# SensorBoardSchm.net
KiCad netlist of a schematic drawn in Altium Designer
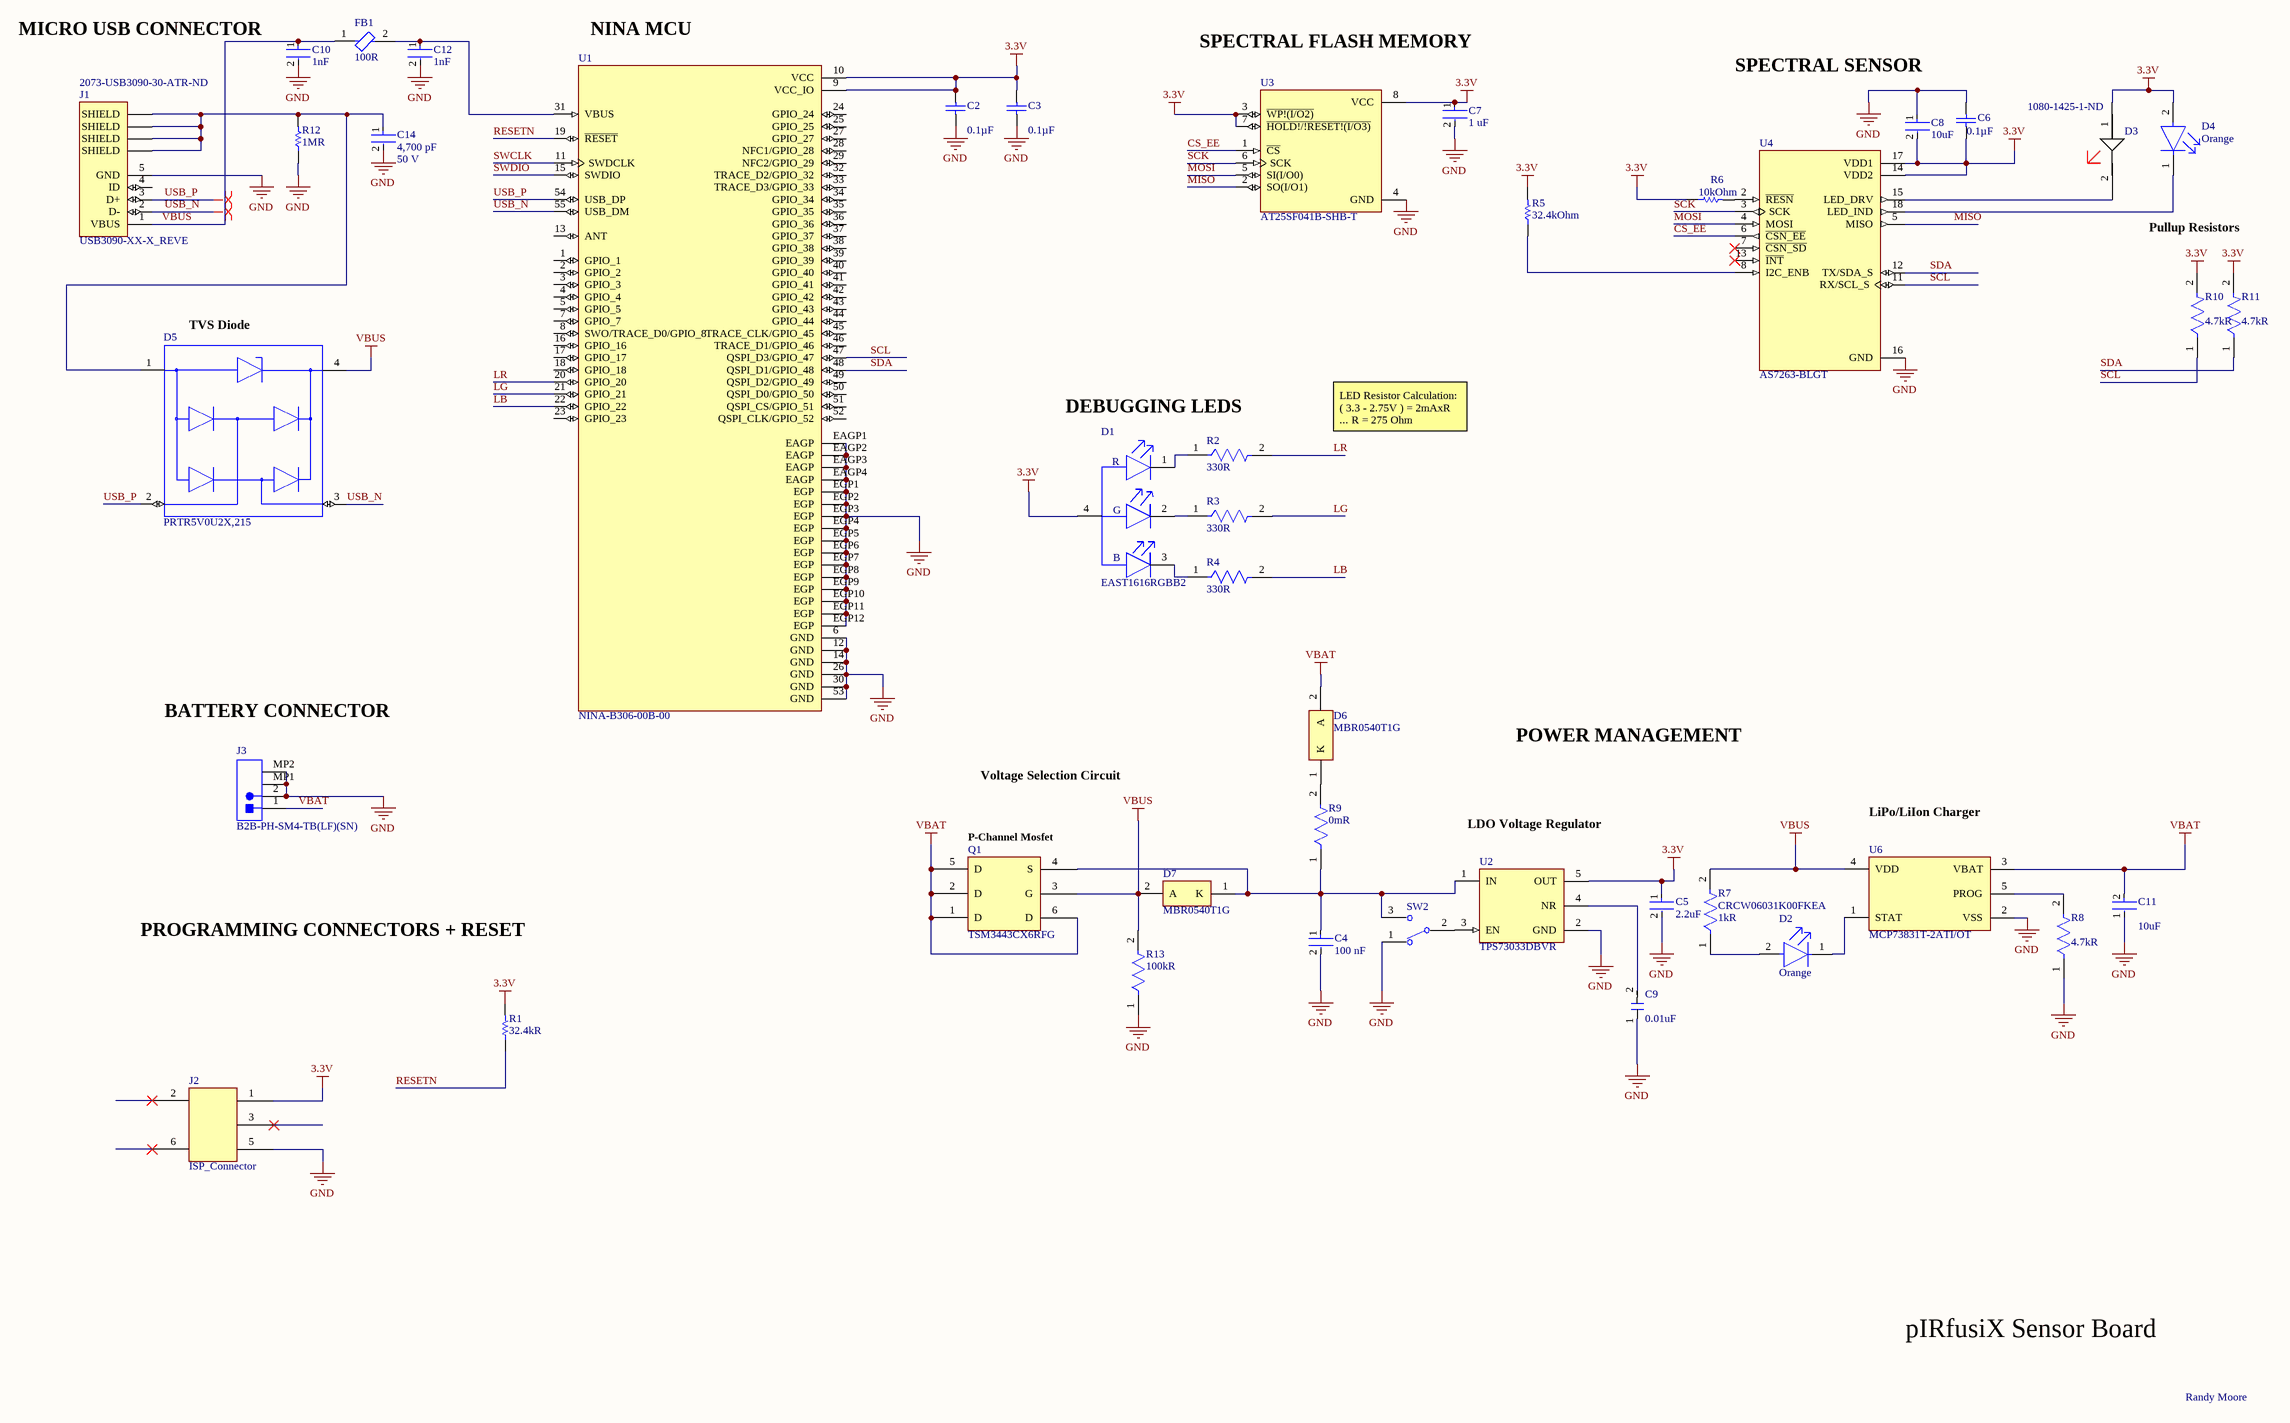
[diagram p0: SensorBoardSchm.SchDoc]

(export (version "E")
  (design (tool "Eeschema 10.0.6"))
  (components
    (comp (ref "C2")
      (value "CL10B104KB8NNNC")
      (footprint "SAMS-C0603-2_M")
      (description "Multi-layer Ceramic Capacitor, -55 to 125 degC, 2-Pin SMD (0603), RoHS, Tape and Reel")
      (fields (field (name "CAPACITANCE") "0.1µF") (field (name "MANUFACTURER") "Samsung Electro-Mechanics"))
      (libsource (lib "Altium Content Vault") (part "CAP-NP-2"))
    )
    (comp (ref "C3")
      (value "CL10B104KB8NNNC")
      (footprint "SAMS-C0603-2_M")
      (description "Multi-layer Ceramic Capacitor, -55 to 125 degC, 2-Pin SMD (0603), RoHS, Tape and Reel")
      (fields (field (name "CAPACITANCE") "0.1µF") (field (name "MANUFACTURER") "Samsung Electro-Mechanics"))
      (libsource (lib "Altium Content Vault") (part "CAP-NP-2"))
    )
    (comp (ref "C4")
      (value "CC0603KRX7R7BB104")
      (footprint "FP-CC0603-DA-MFG")
      (description "CAP CER 0.1UF 16V X7R 0603")
      (fields
        (field (name "OCTOPART") "https://octopart.com/cc0603krx7r7bb104-yageo-192941")
        (field (name "TOLERANCE") "0.1")
        (field (name "CAPACITANCE") "100 nF")
      )
      (libsource (lib "Altium Content Vault") (part "11868f565c42a9108669ba33697ecf6"))
    )
    (comp (ref "C5")
      (value "GRM188R71A225KE15D")
      (footprint "FP-GRM188-0_1-e0_2_0_5-MFG")
      (description "Chip Multilayer Ceramic Capacitors for General Purpose, 0603, 2.2uF, X7R, 15%, 10%, 10V")
      (fields
        (field (name "VOLTAGE") "10V")
        (field (name "CAPACITANCE") "2.2uF")
        (field (name "TOLERANCE") "10%")
      )
      (libsource (lib "Altium Content Vault") (part "11868f565c42a9108669ba33697ecf6"))
    )
    (comp (ref "C6")
      (value "CL10B104KB8NNNC")
      (footprint "SAMS-C0603-2_M")
      (description "Multi-layer Ceramic Capacitor, -55 to 125 degC, 2-Pin SMD (0603), RoHS, Tape and Reel")
      (fields (field (name "CAPACITANCE") "0.1µF") (field (name "MANUFACTURER") "Samsung Electro-Mechanics"))
      (libsource (lib "Altium Content Vault") (part "CAP-NP-2"))
    )
    (comp (ref "C7")
      (value "CC0603KPX7R7BB105")
      (footprint "FP-CC0603-DA-MFG")
      (description "CC0603 1 uF X7R 10.00% 16 V")
      (fields
        (field (name "MANUFACTURER") "YAGEO")
        (field (name "TOLERANCE") "0.1")
        (field (name "CAPACITANCE") "1 uF")
      )
      (libsource (lib "Altium Content Vault") (part "11868f565c42a9108669ba33697ecf6"))
    )
    (comp (ref "C8")
      (value "GRM188R60J106ME47D")
      (footprint "FP-GRM188-0_1-e0_2_0_55-IPC_A")
      (description "Chip Multilayer Ceramic Capacitors for General Purpose, 0603, 10uF, X5R, 15%, 20%, 6.3V")
      (fields
        (field (name "CAPACITANCE") "10uF")
        (field (name "VOLTAGE") "6.3V")
        (field (name "TOLERANCE") "20%")
      )
      (libsource (lib "Altium Content Vault") (part "02cd4be3c70576c341d710602a673aa"))
    )
    (comp (ref "C9")
      (value "C0603C103K3RACTU")
      (footprint "RESC1608X55N")
      (fields (field (name "CAPACITANCE") "0.01uF"))
      (libsource (lib "SensorBoardSchLib") (part "C0603C103K3RACTU"))
    )
    (comp (ref "C10")
      (value "GRM1885C1H102JA01D")
      (footprint "FP-GRM188-0_1-e0_2_0_5-IPC_C")
      (description "Chip Multilayer Ceramic Capacitors for General Purpose, 0603, 1000pF, C0G, 30ppm/°C, 5%, 50V")
      (fields
        (field (name "TOLERANCE") "5%")
        (field (name "CAPACITANCE") "1nF")
        (field (name "VOLTAGE") "50V")
      )
      (libsource (lib "Altium Content Vault") (part "11868f565c42a9108669ba33697ecf6"))
    )
    (comp (ref "C11")
      (value "C1608X5R0J106M080AB")
      (footprint "FP-C1608-080-0_1-MFG")
      (description "Multilayer Ceramic Capacitors 10μF ±20% 6.3V X5R SMD 0603")
      (fields
        (field (name "VOLTAGE") "6.3V")
        (field (name "CAPACITANCE") "10uF")
        (field (name "TOLERANCE") "20%")
      )
      (libsource (lib "Altium Content Vault") (part "236180d848d6139a670b325ea6854c9"))
    )
    (comp (ref "C12")
      (value "GRM1885C1H102JA01D")
      (footprint "FP-GRM188-0_1-e0_2_0_5-IPC_C")
      (description "Chip Multilayer Ceramic Capacitors for General Purpose, 0603, 1000pF, C0G, 30ppm/°C, 5%, 50V")
      (fields
        (field (name "TOLERANCE") "5%")
        (field (name "CAPACITANCE") "1nF")
        (field (name "VOLTAGE") "50V")
      )
      (libsource (lib "Altium Content Vault") (part "11868f565c42a9108669ba33697ecf6"))
    )
    (comp (ref "C14")
      (value "4,700 pF")
      (footprint "FP-C0603C-CF-MFG")
      (description "CAP CER 4700PF 50V 5% NP0 0603")
      (fields
        (field (name "TOLERANCE") "0.05")
        (field (name "OCTOPART") "https://octopart.com/c0603c472j5gactu-kemet-9145067")
        (field (name "VOLTAGE RATING") "50 V")
      )
      (libsource (lib "Altium Content Vault") (part "b4654b650e69147ec39a6b967a45e02"))
    )
    (comp (ref "D1")
      (value "EAST1616RGBB2")
      (footprint "FP-EAST1616RGBB2-MFG")
      (description "LED RGB DIFFUSED 4SMD")
      (fields
        (field (name "OCTOPART") "https://octopart.com/east1616rgbb2-everlight-80328051")
        (field (name "MANUFACTURER") "Everlight")
      )
      (libsource (lib "Altium Content Vault") (part "400868ab6bdf40e56fd99384591646b"))
    )
    (comp (ref "D2")
      (value "TLMO1000-GS08")
      (footprint "FP-6_541-5056_01-4-MFG")
      (description "LED ORANGE 0603 SMD")
      (fields
        (field (name "COLOUR") "Orange")
        (field (name "OCTOPART") "https://octopart.com/tlmo1000-gs08-vishay-41955669")
        (field (name "MANUFACTURER") "Vishay")
      )
      (libsource (lib "Altium Content Vault") (part "8706943c75ba83719d021d2fdc84c58"))
    )
    (comp (ref "D3")
      (value "SIR19-21C/TR8")
      (footprint "SIR19-21C/TR8")
      (fields (field (name "SUPPLIER PART NUMBER 1") "1080-1425-1-ND"))
      (libsource (lib "SensorBoardSchLib") (part "SIR19-21C/TR8"))
    )
    (comp (ref "D4")
      (value "TLMO1000-GS08")
      (footprint "FP-6_541-5056_01-4-MFG")
      (description "LED ORANGE 0603 SMD")
      (fields
        (field (name "COLOUR") "Orange")
        (field (name "OCTOPART") "https://octopart.com/tlmo1000-gs08-vishay-41955669")
        (field (name "MANUFACTURER") "Vishay")
      )
      (libsource (lib "Altium Content Vault") (part "8706943c75ba83719d021d2fdc84c58"))
    )
    (comp (ref "D5")
      (value "PRTR5V0U2X,215")
      (footprint "FP-SOT143B-MFG")
      (description "TVS DIODE 5.5V SOT143B")
      (libsource (lib "Altium Content Vault") (part "31e4fa1655694efd507c8a671e666ef"))
    )
    (comp (ref "D6")
      (value "MBR0540T1G")
      (footprint "ONSC-SOD-123-2-425-04_V")
      (description "Schottky Power Rectifier, 2-Pin SOD-123, Pb-Free, Tape and Reel")
      (fields (field (name "MANUFACTURER") "On Semiconductor"))
      (libsource (lib "Altium Content Vault") (part "ONSC-D-K1A2-2_A"))
    )
    (comp (ref "D7")
      (value "MBR0540T1G")
      (footprint "ONSC-SOD-123-2-425-04_V")
      (description "Schottky Power Rectifier, 2-Pin SOD-123, Pb-Free, Tape and Reel")
      (fields (field (name "MANUFACTURER") "On Semiconductor"))
      (libsource (lib "") (part "ONSC-D-K1A2-2_A_1"))
    )
    (comp (ref "FB1")
      (value "BLM18EG101TN1D")
      (footprint "FP-BLM18-0_15-t0_5-MFG")
      (description "Chip Ferrite Bead, 0603, 100Ω @ 100MHz, 25%, 0.045Ω, 2A")
      (fields (field (name "TOLERANCE") "25%") (field (name "IMPEDANCE") "100R"))
      (libsource (lib "Altium Content Vault") (part "5f30dd21d616792df468990f7003faa"))
    )
    (comp (ref "J1")
      (value "USB3090-XX-X_REVE")
      (footprint "GCT_USB3090-XX-X_REVE")
      (description "USB - micro AB USB 2.0 Receptacle Connector 5 Position Surface Mount, Right Angle; Through Hole")
      (fields
        (field (name "MP") "USB3090-30-A")
        (field (name "MF") "Global Connector Technology")
        (field (name "SUPPLIER PART NUMBER 1") "2073-USB3090-30-ATR-ND")
      )
      (libsource (lib "USB3090-XX-X_REVE") (part "USB3090-XX-X_REVE"))
    )
    (comp (ref "J2")
      (value "ISP_Connector")
      (footprint "JST Programmer")
      (libsource (lib "SensorBoardSchLib") (part "ISP_Connector"))
    )
    (comp (ref "J3")
      (value "B2B-PH-SM4-TB(LF)(SN)")
      (footprint "JST-B2B-PH-SM4-TB-2_V")
      (description "Male Header, Pitch 2 mm, 1 x 2 Position, Height 6.6 mm, RoHS, Tape and Reel")
      (fields (field (name "MANUFACTURER") "JST"))
      (libsource (lib "Altium Content Vault") (part "CN-1P-2M-R2"))
    )
    (comp (ref "Q1")
      (value "TSM3443CX6RFG")
      (footprint "SOT95P280X145-6N")
      (libsource (lib "SensorBoardSchLib") (part "TSM3443CX6RFG"))
    )
    (comp (ref "R1")
      (value "ERJ-3EKF3242V")
      (footprint "RESC1608X55X30ML15T15")
      (fields (field (name "MANUFACTURER") "Panasonic") (field (name "RESISTANCE") "32.4kR"))
      (libsource (lib "Altium Content Vault") (part "RES"))
    )
    (comp (ref "R2")
      (value "CRCW0603330RFKEA")
      (footprint "FP-CRCW0603-e3-MFG")
      (description "RES Thick Film, 330Ω, 1%, 0.1W, 100ppm/°C, 0603")
      (fields (field (name "TOLERANCE") "1%") (field (name "RESISTANCE") "330R"))
      (libsource (lib "Altium Content Vault") (part "1029c3af85768c4190bb7ad29bc67b5"))
    )
    (comp (ref "R3")
      (value "CRCW0603330RFKEA")
      (footprint "FP-CRCW0603-e3-MFG")
      (description "RES Thick Film, 330Ω, 1%, 0.1W, 100ppm/°C, 0603")
      (fields (field (name "TOLERANCE") "1%") (field (name "RESISTANCE") "330R"))
      (libsource (lib "Altium Content Vault") (part "1029c3af85768c4190bb7ad29bc67b5"))
    )
    (comp (ref "R4")
      (value "CRCW0603330RFKEA")
      (footprint "FP-CRCW0603-e3-MFG")
      (description "RES Thick Film, 330Ω, 1%, 0.1W, 100ppm/°C, 0603")
      (fields (field (name "TOLERANCE") "1%") (field (name "RESISTANCE") "330R"))
      (libsource (lib "Altium Content Vault") (part "1029c3af85768c4190bb7ad29bc67b5"))
    )
    (comp (ref "R5")
      (value "ERJ-3EKF3242V")
      (footprint "RESC1608X55X30ML15T15")
      (fields (field (name "MANUFACTURER") "Panasonic") (field (name "RESISTANCE") "32.4kOhm"))
      (libsource (lib "Altium Content Vault") (part "RES"))
    )
    (comp (ref "R6")
      (value "CRCW060310K0FKTB")
      (footprint "RESC1609X50X30ML10T20")
      (fields (field (name "MANUFACTURER") "Vishay Dale") (field (name "RESISTANCE") "10kOhm"))
      (libsource (lib "Altium Content Vault") (part "RES"))
    )
    (comp (ref "R7")
      (value "CRCW06031K00FKEA")
      (footprint "FP-CRCW0603-e3-MFG")
      (description "RES Thick Film, 1kΩ, 1%, 0.1W, 100ppm/°C, 0603")
      (fields (field (name "TOLERANCE") "1%") (field (name "RESISTANCE") "1kR"))
      (libsource (lib "Altium Content Vault") (part "1029c3af85768c4190bb7ad29bc67b5"))
    )
    (comp (ref "R8")
      (value "CR0603-FX-4701ELF")
      (footprint "FP-CR0603-IPC_B")
      (description "Thick Film Chip Resistors 0603 4.7kΩ 0.1W 1% 100ppm/°C")
      (fields (field (name "RESISTANCE") "4.7kR") (field (name "TOLERANCE") "1%"))
      (libsource (lib "Altium Content Vault") (part "1029c3af85768c4190bb7ad29bc67b5"))
    )
    (comp (ref "R9")
      (value "CRCW06030000Z0EAHP")
      (footprint "FP-CRCW0603-HPe3-MFG")
      (description "RES Thick Film, 0Ω, , 0.33W, , 0603")
      (fields (field (name "RESISTANCE") "0mR"))
      (libsource (lib "Altium Content Vault") (part "1029c3af85768c4190bb7ad29bc67b5"))
    )
    (comp (ref "R10")
      (value "CR0603-FX-4701ELF")
      (footprint "FP-CR0603-IPC_B")
      (description "Thick Film Chip Resistors 0603 4.7kΩ 0.1W 1% 100ppm/°C")
      (fields (field (name "RESISTANCE") "4.7kR") (field (name "TOLERANCE") "1%"))
      (libsource (lib "Altium Content Vault") (part "1029c3af85768c4190bb7ad29bc67b5"))
    )
    (comp (ref "R11")
      (value "CR0603-FX-4701ELF")
      (footprint "FP-CR0603-IPC_B")
      (description "Thick Film Chip Resistors 0603 4.7kΩ 0.1W 1% 100ppm/°C")
      (fields (field (name "RESISTANCE") "4.7kR") (field (name "TOLERANCE") "1%"))
      (libsource (lib "Altium Content Vault") (part "1029c3af85768c4190bb7ad29bc67b5"))
    )
    (comp (ref "R12")
      (value "RC0603FR-071ML")
      (footprint "RESC1608X55X25LL10T15")
      (description "Chip Resistor, 1 MOhm, +/- 1%, 100 mW, -55 to 155 degC, 0603 (1608 Metric), RoHS, Tape and Reel")
      (fields (field (name "TOLERANCE") "20%") (field (name "RESISTANCE") "1MR"))
      (libsource (lib "Altium Content Vault") (part "RES-2"))
    )
    (comp (ref "R13")
      (value "RC0603FR-07100KL")
      (footprint "FP-RC0603-0_55-MFG")
      (description "RES SMD 100K OHM 1% 1/10W 0603")
      (fields (field (name "RESISTANCE") "100kR") (field (name "TOLERANCE") "1%"))
      (libsource (lib "Altium Content Vault") (part "1029c3af85768c4190bb7ad29bc67b5"))
    )
    (comp (ref "SW2")
      (value "JS102011JAQN")
      (footprint "FP-JS102011JAQN-MFG")
      (description "SWITCH SLIDE SPDT 300MA 6V")
      (fields
        (field (name "MANUFACTURER") "C&K")
        (field (name "OCTOPART") "https://octopart.com/js102011jaqn-c%26k+components-74831566")
      )
      (libsource (lib "Altium Content Vault") (part "3307bfe30257a22cc26f07bdba41a07"))
    )
    (comp (ref "U1")
      (value "NINA-B306-00B-00")
      (footprint "XCVR_NINA-B306-00B-00")
      (description "With internal PCB antenna, 10.0 x 15.0 x 2.2 mm, use with open CPU")
      (fields (field (name "MF") "u-blox"))
      (libsource (lib "SensorBoardSchLib") (part "NINA-B306-00B-00"))
    )
    (comp (ref "U2")
      (value "TPS73033DBVR")
      (footprint "FP-DBV0005A-MFG")
      (description "IC REG LINEAR 3.3V 200MA SOT23-5")
      (fields
        (field (name "OCTOPART") "https://octopart.com/tps73033dbvr-texas+instruments-525554")
        (field (name "MANUFACTURER") "Texas Instruments")
      )
      (libsource (lib "Altium Content Vault") (part "be1415fd5a6e884120ed371e1ec99d7"))
    )
    (comp (ref "U3")
      (value "AT25SF041B-SHB-T")
      (footprint "SOIC127P790X216-8N")
      (fields (field (name "MF") "Dialog Semiconductor"))
      (libsource (lib "SensorBoardSchLib") (part "AT25SF041B-SHB-T"))
    )
    (comp (ref "U4")
      (value "AS7263-BLGT")
      (footprint "AS7263Footprint")
      (description "Optical Sensor Ambient 610nm, 680nm, 730nm, 760nm, 810nm, 860nm IÂ²C, SPI 20-BFLGA")
      (fields (field (name "MF") "ams"))
      (libsource (lib "AS7263-BLGT (1)") (part "AS7263-BLGT"))
    )
    (comp (ref "U6")
      (value "MCP73831T-2ATI/OT")
      (footprint "FP-C04-091-OT-IPC_C")
      (description "IC CONTROLLR LI-ION 4.2V SOT23-5")
      (libsource (lib "Altium Content Vault") (part "a15496f3f0dd9906c1bee5f8dba5d2c"))
    )
  )
  (nets
    (net (code "1") (name "/CS_EE") (class "Default")
      (node (ref "U3") (pin "1") (pinfunction "~{CS}_1") (pintype "input"))
      (node (ref "U4") (pin "6") (pinfunction "~{CSN_EE}_6") (pintype "output"))
    )
    (net (code "2") (name "/LB") (class "Default")
      (node (ref "R4") (pin "2") (pinfunction "2_2") (pintype "passive"))
      (node (ref "U1") (pin "22") (pinfunction "GPIO_22_22") (pintype "bidirectional"))
    )
    (net (code "3") (name "/LG") (class "Default")
      (node (ref "R3") (pin "2") (pinfunction "2_2") (pintype "passive"))
      (node (ref "U1") (pin "21") (pinfunction "GPIO_21_21") (pintype "bidirectional"))
    )
    (net (code "4") (name "/LR") (class "Default")
      (node (ref "R2") (pin "2") (pinfunction "2_2") (pintype "passive"))
      (node (ref "U1") (pin "20") (pinfunction "GPIO_20_20") (pintype "bidirectional"))
    )
    (net (code "5") (name "/MISO") (class "Default")
      (node (ref "U3") (pin "2") (pinfunction "SO(I/O1)_2") (pintype "bidirectional"))
      (node (ref "U4") (pin "5") (pinfunction "MISO_5") (pintype "output"))
    )
    (net (code "6") (name "/MOSI") (class "Default")
      (node (ref "U3") (pin "5") (pinfunction "SI(I/O0)_5") (pintype "bidirectional"))
      (node (ref "U4") (pin "4") (pinfunction "MOSI_4") (pintype "input"))
    )
    (net (code "7") (name "/RESETN") (class "Default")
      (node (ref "R1") (pin "1") (pinfunction "1_1") (pintype "passive"))
      (node (ref "U1") (pin "19") (pinfunction "~{RESET}_19") (pintype "bidirectional"))
    )
    (net (code "8") (name "/SCK") (class "Default")
      (node (ref "U3") (pin "6") (pinfunction "SCK_6") (pintype "input"))
      (node (ref "U4") (pin "3") (pinfunction "SCK_3") (pintype "output"))
    )
    (net (code "9") (name "/SCL") (class "Default")
      (node (ref "R10") (pin "1") (pinfunction "1_1") (pintype "passive"))
      (node (ref "U1") (pin "47") (pinfunction "QSPI_D3/GPIO_47_47") (pintype "bidirectional"))
      (node (ref "U4") (pin "11") (pinfunction "RX/SCL_S_11") (pintype "bidirectional"))
    )
    (net (code "10") (name "/SDA") (class "Default")
      (node (ref "R11") (pin "1") (pinfunction "1_1") (pintype "passive"))
      (node (ref "U1") (pin "48") (pinfunction "QSPI_D1/GPIO_48_48") (pintype "bidirectional"))
      (node (ref "U4") (pin "12") (pinfunction "TX/SDA_S_12") (pintype "bidirectional"))
    )
    (net (code "11") (name "/SWCLK") (class "Default")
      (node (ref "U1") (pin "11") (pinfunction "SWDCLK_11") (pintype "input"))
    )
    (net (code "12") (name "/SWDIO") (class "Default")
      (node (ref "U1") (pin "15") (pinfunction "SWDIO_15") (pintype "bidirectional"))
    )
    (net (code "13") (name "/USB_N") (class "Default")
      (node (ref "D5") (pin "3") (pinfunction "I/O_2_3") (pintype "bidirectional"))
      (node (ref "J1") (pin "2") (pinfunction "D-_2") (pintype "bidirectional"))
      (node (ref "U1") (pin "55") (pinfunction "USB_DM_55") (pintype "bidirectional"))
    )
    (net (code "14") (name "/USB_P") (class "Default")
      (node (ref "D5") (pin "2") (pinfunction "I/O_1_2") (pintype "bidirectional"))
      (node (ref "J1") (pin "3") (pinfunction "D+_3") (pintype "bidirectional"))
      (node (ref "U1") (pin "54") (pinfunction "USB_DP_54") (pintype "bidirectional"))
    )
    (net (code "15") (name "3.3V") (class "Default")
      (node (ref "C2") (pin "2") (pinfunction "2_2") (pintype "passive"))
      (node (ref "C3") (pin "2") (pinfunction "2_2") (pintype "passive"))
      (node (ref "C5") (pin "1") (pinfunction "1_1") (pintype "passive"))
      (node (ref "C6") (pin "1") (pinfunction "1_1") (pintype "passive"))
      (node (ref "C7") (pin "1") (pinfunction "1_1") (pintype "passive"))
      (node (ref "C8") (pin "2") (pinfunction "2_2") (pintype "passive"))
      (node (ref "D1") (pin "4") (pinfunction "Common_Anode_4") (pintype "passive"))
      (node (ref "D3") (pin "1") (pinfunction "1_1") (pintype "passive"))
      (node (ref "D4") (pin "2") (pinfunction "A_2") (pintype "passive"))
      (node (ref "J2") (pin "1") (pinfunction "VDD_1") (pintype "passive"))
      (node (ref "R1") (pin "2") (pinfunction "2_2") (pintype "passive"))
      (node (ref "R10") (pin "2") (pinfunction "2_2") (pintype "passive"))
      (node (ref "R11") (pin "2") (pinfunction "2_2") (pintype "passive"))
      (node (ref "R5") (pin "2") (pinfunction "2_2") (pintype "passive"))
      (node (ref "R6") (pin "1") (pinfunction "1_1") (pintype "passive"))
      (node (ref "U1") (pin "10") (pinfunction "VCC_10") (pintype "power_in"))
      (node (ref "U1") (pin "9") (pinfunction "VCC_IO_9") (pintype "power_in"))
      (node (ref "U2") (pin "5") (pinfunction "OUT_5") (pintype "power_in"))
      (node (ref "U3") (pin "3") (pinfunction "~{WP!(I/O2)}_3") (pintype "bidirectional"))
      (node (ref "U3") (pin "7") (pinfunction "~{HOLD!/!RESET!(I/O3)}_7") (pintype "bidirectional"))
      (node (ref "U3") (pin "8") (pinfunction "VCC_8") (pintype "power_in"))
      (node (ref "U4") (pin "14") (pinfunction "VDD2_14") (pintype "power_in"))
      (node (ref "U4") (pin "17") (pinfunction "VDD1_17") (pintype "power_in"))
    )
    (net (code "16") (name "GND") (class "Default")
      (node (ref "C10") (pin "2") (pinfunction "2_2") (pintype "passive"))
      (node (ref "C11") (pin "1") (pinfunction "1_1") (pintype "passive"))
      (node (ref "C12") (pin "2") (pinfunction "2_2") (pintype "passive"))
      (node (ref "C14") (pin "2") (pinfunction "2_2") (pintype "passive"))
      (node (ref "C2") (pin "1") (pinfunction "1_1") (pintype "passive"))
      (node (ref "C3") (pin "1") (pinfunction "1_1") (pintype "passive"))
      (node (ref "C4") (pin "2") (pinfunction "2_2") (pintype "passive"))
      (node (ref "C5") (pin "2") (pinfunction "2_2") (pintype "passive"))
      (node (ref "C6") (pin "2") (pinfunction "2_2") (pintype "passive"))
      (node (ref "C7") (pin "2") (pinfunction "2_2") (pintype "passive"))
      (node (ref "C8") (pin "1") (pinfunction "1_1") (pintype "passive"))
      (node (ref "C9") (pin "1") (pintype "passive"))
      (node (ref "J1") (pin "5") (pinfunction "GND_5") (pintype "power_in"))
      (node (ref "J2") (pin "5") (pinfunction "GND_5") (pintype "passive"))
      (node (ref "J3") (pin "2") (pinfunction "2_2") (pintype "passive"))
      (node (ref "J3") (pin "MP1") (pinfunction "MP1_MP1") (pintype "passive"))
      (node (ref "J3") (pin "MP2") (pinfunction "MP2_MP2") (pintype "passive"))
      (node (ref "R12") (pin "1") (pinfunction "1_1") (pintype "passive"))
      (node (ref "R13") (pin "1") (pinfunction "1_1") (pintype "passive"))
      (node (ref "R8") (pin "1") (pinfunction "1_1") (pintype "passive"))
      (node (ref "SW2") (pin "1") (pinfunction "1_1") (pintype "passive"))
      (node (ref "U1") (pin "12") (pinfunction "GND_12") (pintype "power_in"))
      (node (ref "U1") (pin "14") (pinfunction "GND_14") (pintype "power_in"))
      (node (ref "U1") (pin "26") (pinfunction "GND_26") (pintype "power_in"))
      (node (ref "U1") (pin "30") (pinfunction "GND_30") (pintype "power_in"))
      (node (ref "U1") (pin "53") (pinfunction "GND_53") (pintype "power_in"))
      (node (ref "U1") (pin "6") (pinfunction "GND_6") (pintype "power_in"))
      (node (ref "U1") (pin "EAGP1") (pinfunction "EAGP_EAGP1") (pintype "power_in"))
      (node (ref "U1") (pin "EAGP2") (pinfunction "EAGP_EAGP2") (pintype "power_in"))
      (node (ref "U1") (pin "EAGP3") (pinfunction "EAGP_EAGP3") (pintype "power_in"))
      (node (ref "U1") (pin "EAGP4") (pinfunction "EAGP_EAGP4") (pintype "power_in"))
      (node (ref "U1") (pin "EGP1") (pinfunction "EGP_EGP1") (pintype "power_in"))
      (node (ref "U1") (pin "EGP10") (pinfunction "EGP_EGP10") (pintype "power_in"))
      (node (ref "U1") (pin "EGP11") (pinfunction "EGP_EGP11") (pintype "power_in"))
      (node (ref "U1") (pin "EGP12") (pinfunction "EGP_EGP12") (pintype "power_in"))
      (node (ref "U1") (pin "EGP2") (pinfunction "EGP_EGP2") (pintype "power_in"))
      (node (ref "U1") (pin "EGP3") (pinfunction "EGP_EGP3") (pintype "power_in"))
      (node (ref "U1") (pin "EGP4") (pinfunction "EGP_EGP4") (pintype "power_in"))
      (node (ref "U1") (pin "EGP5") (pinfunction "EGP_EGP5") (pintype "power_in"))
      (node (ref "U1") (pin "EGP6") (pinfunction "EGP_EGP6") (pintype "power_in"))
      (node (ref "U1") (pin "EGP7") (pinfunction "EGP_EGP7") (pintype "power_in"))
      (node (ref "U1") (pin "EGP8") (pinfunction "EGP_EGP8") (pintype "power_in"))
      (node (ref "U1") (pin "EGP9") (pinfunction "EGP_EGP9") (pintype "power_in"))
      (node (ref "U2") (pin "2") (pinfunction "GND_2") (pintype "power_in"))
      (node (ref "U3") (pin "4") (pinfunction "GND_4") (pintype "power_in"))
      (node (ref "U4") (pin "16") (pinfunction "GND_16") (pintype "power_in"))
      (node (ref "U6") (pin "2") (pinfunction "VSS_2") (pintype "power_in"))
    )
    (net (code "17") (name "Net-(D1-Blue_C)") (class "Default")
      (node (ref "D1") (pin "3") (pinfunction "Blue_C_3") (pintype "passive"))
      (node (ref "R4") (pin "1") (pinfunction "1_1") (pintype "passive"))
    )
    (net (code "18") (name "Net-(D1-Green_C)") (class "Default")
      (node (ref "D1") (pin "2") (pinfunction "Green_C_2") (pintype "passive"))
      (node (ref "R3") (pin "1") (pinfunction "1_1") (pintype "passive"))
    )
    (net (code "19") (name "Net-(D1-Red_C)") (class "Default")
      (node (ref "D1") (pin "1") (pinfunction "Red_C_1") (pintype "passive"))
      (node (ref "R2") (pin "1") (pinfunction "1_1") (pintype "passive"))
    )
    (net (code "20") (name "Net-(D2-A)") (class "Default")
      (node (ref "D2") (pin "2") (pinfunction "A_2") (pintype "passive"))
      (node (ref "R7") (pin "1") (pinfunction "1_1") (pintype "passive"))
    )
    (net (code "21") (name "Net-(D2-C)") (class "Default")
      (node (ref "D2") (pin "1") (pinfunction "C_1") (pintype "passive"))
      (node (ref "U6") (pin "1") (pinfunction "STAT_1") (pintype "passive"))
    )
    (net (code "22") (name "Net-(D4-C)") (class "Default")
      (node (ref "D4") (pin "1") (pinfunction "C_1") (pintype "passive"))
      (node (ref "U4") (pin "18") (pinfunction "LED_IND_18") (pintype "output"))
    )
    (net (code "23") (name "Net-(D5-GND)") (class "Default")
      (node (ref "C14") (pin "1") (pinfunction "1_1") (pintype "passive"))
      (node (ref "D5") (pin "1") (pinfunction "GND_1") (pintype "power_in"))
      (node (ref "J1") (pin "6") (pinfunction "SHIELD_6") (pintype "power_in"))
      (node (ref "J1") (pin "7") (pinfunction "SHIELD_7") (pintype "power_in"))
      (node (ref "J1") (pin "8") (pinfunction "SHIELD_8") (pintype "power_in"))
      (node (ref "J1") (pin "9") (pinfunction "SHIELD_9") (pintype "power_in"))
      (node (ref "R12") (pin "2") (pinfunction "2_2") (pintype "passive"))
    )
    (net (code "24") (name "Net-(D6-K)") (class "Default")
      (node (ref "D6") (pin "1") (pinfunction "K_1") (pintype "passive"))
      (node (ref "R9") (pin "2") (pinfunction "2_2") (pintype "passive"))
    )
    (net (code "25") (name "Net-(D7-K)") (class "Default")
      (node (ref "C4") (pin "1") (pinfunction "1_1") (pintype "passive"))
      (node (ref "D7") (pin "1") (pinfunction "K_1") (pintype "passive"))
      (node (ref "Q1") (pin "4") (pinfunction "S_4") (pintype "passive"))
      (node (ref "R9") (pin "1") (pinfunction "1_1") (pintype "passive"))
      (node (ref "SW2") (pin "3") (pinfunction "3_3") (pintype "passive"))
      (node (ref "U2") (pin "1") (pinfunction "IN_1") (pintype "power_in"))
    )
    (net (code "26") (name "Net-(SW2-C)") (class "Default")
      (node (ref "SW2") (pin "2") (pinfunction "C_2") (pintype "passive"))
      (node (ref "U2") (pin "3") (pinfunction "EN_3") (pintype "input"))
    )
    (net (code "27") (name "Net-(U1-VBUS)") (class "Default")
      (node (ref "C12") (pin "1") (pinfunction "1_1") (pintype "passive"))
      (node (ref "FB1") (pin "2") (pinfunction "2_2") (pintype "passive"))
      (node (ref "U1") (pin "31") (pinfunction "VBUS_31") (pintype "input"))
    )
    (net (code "28") (name "Net-(U2-NR)") (class "Default")
      (node (ref "C9") (pin "2") (pintype "passive"))
      (node (ref "U2") (pin "4") (pinfunction "NR_4") (pintype "passive"))
    )
    (net (code "29") (name "Net-(U4-I2C_ENB)") (class "Default")
      (node (ref "R5") (pin "1") (pinfunction "1_1") (pintype "passive"))
      (node (ref "U4") (pin "8") (pinfunction "I2C_ENB_8") (pintype "input"))
    )
    (net (code "30") (name "Net-(U4-LED_DRV)") (class "Default")
      (node (ref "D3") (pin "2") (pinfunction "2_2") (pintype "passive"))
      (node (ref "U4") (pin "15") (pinfunction "LED_DRV_15") (pintype "output"))
    )
    (net (code "31") (name "Net-(U4-~{RESN})") (class "Default")
      (node (ref "R6") (pin "2") (pinfunction "2_2") (pintype "passive"))
      (node (ref "U4") (pin "2") (pinfunction "~{RESN}_2") (pintype "input"))
    )
    (net (code "32") (name "Net-(U6-PROG)") (class "Default")
      (node (ref "R8") (pin "2") (pinfunction "2_2") (pintype "passive"))
      (node (ref "U6") (pin "5") (pinfunction "PROG_5") (pintype "passive"))
    )
    (net (code "33") (name "VBAT") (class "Default")
      (node (ref "C11") (pin "2") (pinfunction "2_2") (pintype "passive"))
      (node (ref "D6") (pin "2") (pinfunction "A_2") (pintype "passive"))
      (node (ref "J3") (pin "1") (pinfunction "1_1") (pintype "passive"))
      (node (ref "Q1") (pin "1") (pinfunction "D_1") (pintype "passive"))
      (node (ref "Q1") (pin "2") (pinfunction "D_2") (pintype "passive"))
      (node (ref "Q1") (pin "5") (pinfunction "D_5") (pintype "passive"))
      (node (ref "Q1") (pin "6") (pinfunction "D_6") (pintype "passive"))
      (node (ref "U6") (pin "3") (pinfunction "VBAT_3") (pintype "power_in"))
    )
    (net (code "34") (name "VBUS") (class "Default")
      (node (ref "C10") (pin "1") (pinfunction "1_1") (pintype "passive"))
      (node (ref "D5") (pin "4") (pinfunction "VCC_4") (pintype "power_in"))
      (node (ref "D7") (pin "2") (pinfunction "A_2") (pintype "passive"))
      (node (ref "FB1") (pin "1") (pinfunction "1_1") (pintype "passive"))
      (node (ref "J1") (pin "1") (pinfunction "VBUS_1") (pintype "power_in"))
      (node (ref "Q1") (pin "3") (pinfunction "G_3") (pintype "passive"))
      (node (ref "R13") (pin "2") (pinfunction "2_2") (pintype "passive"))
      (node (ref "R7") (pin "2") (pinfunction "2_2") (pintype "passive"))
      (node (ref "U6") (pin "4") (pinfunction "VDD_4") (pintype "power_in"))
    )
    (net (code "35") (name "unconnected-(J1-ID-Pad4)") (class "Default")
      (node (ref "J1") (pin "4") (pinfunction "ID_4") (pintype "bidirectional"))
    )
    (net (code "36") (name "unconnected-(J2-RESETN-Pad6)") (class "Default")
      (node (ref "J2") (pin "6") (pinfunction "RESETN_6") (pintype "passive+no_connect"))
    )
    (net (code "37") (name "unconnected-(J2-SWCLK-Pad3)") (class "Default")
      (node (ref "J2") (pin "3") (pinfunction "SWCLK_3") (pintype "passive+no_connect"))
    )
    (net (code "38") (name "unconnected-(J2-SWDIO-Pad2)") (class "Default")
      (node (ref "J2") (pin "2") (pinfunction "SWDIO_2") (pintype "passive+no_connect"))
    )
    (net (code "39") (name "unconnected-(U1-ANT-Pad13)") (class "Default")
      (node (ref "U1") (pin "13") (pinfunction "ANT_13") (pintype "bidirectional"))
    )
    (net (code "40") (name "unconnected-(U1-GPIO_1-Pad1)") (class "Default")
      (node (ref "U1") (pin "1") (pinfunction "GPIO_1_1") (pintype "bidirectional"))
    )
    (net (code "41") (name "unconnected-(U1-GPIO_2-Pad2)") (class "Default")
      (node (ref "U1") (pin "2") (pinfunction "GPIO_2_2") (pintype "bidirectional"))
    )
    (net (code "42") (name "unconnected-(U1-GPIO_3-Pad3)") (class "Default")
      (node (ref "U1") (pin "3") (pinfunction "GPIO_3_3") (pintype "bidirectional"))
    )
    (net (code "43") (name "unconnected-(U1-GPIO_4-Pad4)") (class "Default")
      (node (ref "U1") (pin "4") (pinfunction "GPIO_4_4") (pintype "bidirectional"))
    )
    (net (code "44") (name "unconnected-(U1-GPIO_5-Pad5)") (class "Default")
      (node (ref "U1") (pin "5") (pinfunction "GPIO_5_5") (pintype "bidirectional"))
    )
    (net (code "45") (name "unconnected-(U1-GPIO_7-Pad7)") (class "Default")
      (node (ref "U1") (pin "7") (pinfunction "GPIO_7_7") (pintype "bidirectional"))
    )
    (net (code "46") (name "unconnected-(U1-GPIO_16-Pad16)") (class "Default")
      (node (ref "U1") (pin "16") (pinfunction "GPIO_16_16") (pintype "bidirectional"))
    )
    (net (code "47") (name "unconnected-(U1-GPIO_17-Pad17)") (class "Default")
      (node (ref "U1") (pin "17") (pinfunction "GPIO_17_17") (pintype "bidirectional"))
    )
    (net (code "48") (name "unconnected-(U1-GPIO_18-Pad18)") (class "Default")
      (node (ref "U1") (pin "18") (pinfunction "GPIO_18_18") (pintype "bidirectional"))
    )
    (net (code "49") (name "unconnected-(U1-GPIO_23-Pad23)") (class "Default")
      (node (ref "U1") (pin "23") (pinfunction "GPIO_23_23") (pintype "bidirectional"))
    )
    (net (code "50") (name "unconnected-(U1-GPIO_24-Pad24)") (class "Default")
      (node (ref "U1") (pin "24") (pinfunction "GPIO_24_24") (pintype "bidirectional"))
    )
    (net (code "51") (name "unconnected-(U1-GPIO_25-Pad25)") (class "Default")
      (node (ref "U1") (pin "25") (pinfunction "GPIO_25_25") (pintype "bidirectional"))
    )
    (net (code "52") (name "unconnected-(U1-GPIO_27-Pad27)") (class "Default")
      (node (ref "U1") (pin "27") (pinfunction "GPIO_27_27") (pintype "bidirectional"))
    )
    (net (code "53") (name "unconnected-(U1-GPIO_34-Pad34)") (class "Default")
      (node (ref "U1") (pin "34") (pinfunction "GPIO_34_34") (pintype "bidirectional"))
    )
    (net (code "54") (name "unconnected-(U1-GPIO_35-Pad35)") (class "Default")
      (node (ref "U1") (pin "35") (pinfunction "GPIO_35_35") (pintype "bidirectional"))
    )
    (net (code "55") (name "unconnected-(U1-GPIO_36-Pad36)") (class "Default")
      (node (ref "U1") (pin "36") (pinfunction "GPIO_36_36") (pintype "bidirectional"))
    )
    (net (code "56") (name "unconnected-(U1-GPIO_37-Pad37)") (class "Default")
      (node (ref "U1") (pin "37") (pinfunction "GPIO_37_37") (pintype "bidirectional"))
    )
    (net (code "57") (name "unconnected-(U1-GPIO_38-Pad38)") (class "Default")
      (node (ref "U1") (pin "38") (pinfunction "GPIO_38_38") (pintype "bidirectional"))
    )
    (net (code "58") (name "unconnected-(U1-GPIO_39-Pad39)") (class "Default")
      (node (ref "U1") (pin "39") (pinfunction "GPIO_39_39") (pintype "bidirectional"))
    )
    (net (code "59") (name "unconnected-(U1-GPIO_40-Pad40)") (class "Default")
      (node (ref "U1") (pin "40") (pinfunction "GPIO_40_40") (pintype "bidirectional"))
    )
    (net (code "60") (name "unconnected-(U1-GPIO_41-Pad41)") (class "Default")
      (node (ref "U1") (pin "41") (pinfunction "GPIO_41_41") (pintype "bidirectional"))
    )
    (net (code "61") (name "unconnected-(U1-GPIO_42-Pad42)") (class "Default")
      (node (ref "U1") (pin "42") (pinfunction "GPIO_42_42") (pintype "bidirectional"))
    )
    (net (code "62") (name "unconnected-(U1-GPIO_43-Pad43)") (class "Default")
      (node (ref "U1") (pin "43") (pinfunction "GPIO_43_43") (pintype "bidirectional"))
    )
    (net (code "63") (name "unconnected-(U1-GPIO_44-Pad44)") (class "Default")
      (node (ref "U1") (pin "44") (pinfunction "GPIO_44_44") (pintype "bidirectional"))
    )
    (net (code "64") (name "unconnected-(U1-NFC1{slash}GPIO_28-Pad28)") (class "Default")
      (node (ref "U1") (pin "28") (pinfunction "NFC1/GPIO_28_28") (pintype "bidirectional"))
    )
    (net (code "65") (name "unconnected-(U1-NFC2{slash}GPIO_29-Pad29)") (class "Default")
      (node (ref "U1") (pin "29") (pinfunction "NFC2/GPIO_29_29") (pintype "bidirectional"))
    )
    (net (code "66") (name "unconnected-(U1-QSPI_CLK{slash}GPIO_52-Pad52)") (class "Default")
      (node (ref "U1") (pin "52") (pinfunction "QSPI_CLK/GPIO_52_52") (pintype "bidirectional"))
    )
    (net (code "67") (name "unconnected-(U1-QSPI_CS{slash}GPIO_51-Pad51)") (class "Default")
      (node (ref "U1") (pin "51") (pinfunction "QSPI_CS/GPIO_51_51") (pintype "bidirectional"))
    )
    (net (code "68") (name "unconnected-(U1-QSPI_D0{slash}GPIO_50-Pad50)") (class "Default")
      (node (ref "U1") (pin "50") (pinfunction "QSPI_D0/GPIO_50_50") (pintype "bidirectional"))
    )
    (net (code "69") (name "unconnected-(U1-QSPI_D2{slash}GPIO_49-Pad49)") (class "Default")
      (node (ref "U1") (pin "49") (pinfunction "QSPI_D2/GPIO_49_49") (pintype "bidirectional"))
    )
    (net (code "70") (name "unconnected-(U1-SWO{slash}TRACE_D0{slash}GPIO_8-Pad8)") (class "Default")
      (node (ref "U1") (pin "8") (pinfunction "SWO/TRACE_D0/GPIO_8_8") (pintype "bidirectional"))
    )
    (net (code "71") (name "unconnected-(U1-TRACE_CLK{slash}GPIO_45-Pad45)") (class "Default")
      (node (ref "U1") (pin "45") (pinfunction "TRACE_CLK/GPIO_45_45") (pintype "bidirectional"))
    )
    (net (code "72") (name "unconnected-(U1-TRACE_D1{slash}GPIO_46-Pad46)") (class "Default")
      (node (ref "U1") (pin "46") (pinfunction "TRACE_D1/GPIO_46_46") (pintype "bidirectional"))
    )
    (net (code "73") (name "unconnected-(U1-TRACE_D2{slash}GPIO_32-Pad32)") (class "Default")
      (node (ref "U1") (pin "32") (pinfunction "TRACE_D2/GPIO_32_32") (pintype "bidirectional"))
    )
    (net (code "74") (name "unconnected-(U1-TRACE_D3{slash}GPIO_33-Pad33)") (class "Default")
      (node (ref "U1") (pin "33") (pinfunction "TRACE_D3/GPIO_33_33") (pintype "bidirectional"))
    )
    (net (code "75") (name "unconnected-(U4-~{CSN_SD}-Pad7)") (class "Default")
      (node (ref "U4") (pin "7") (pinfunction "~{CSN_SD}_7") (pintype "input+no_connect"))
    )
    (net (code "76") (name "unconnected-(U4-~{INT}-Pad13)") (class "Default")
      (node (ref "U4") (pin "13") (pinfunction "~{INT}_13") (pintype "input+no_connect"))
    )
  )
)
